# CV_slew_limiter_copy.net
KiCad netlist of a schematic drawn in EAGLE
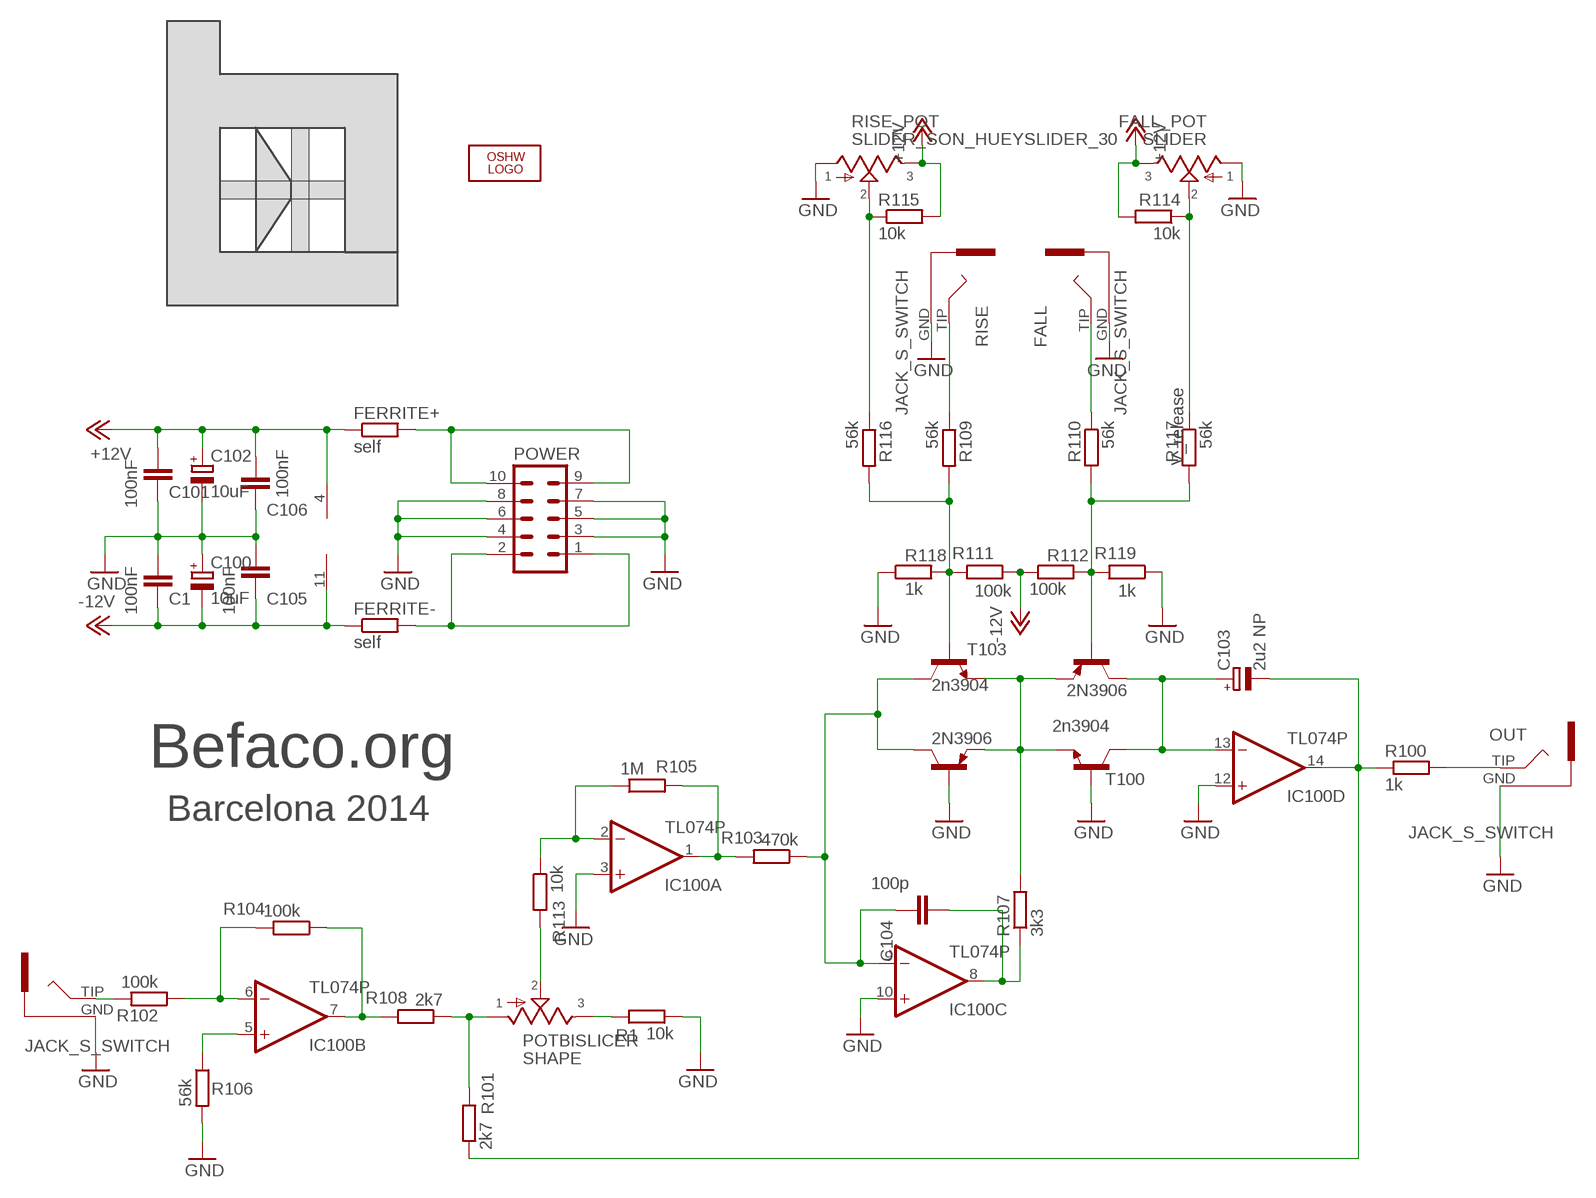
[diagram p0: schematic, sheet 1]

(export (version "E")
  (design (tool "Eeschema 10.0.6"))
  (components
    (comp (ref "C1")
      (value "100nF")
      (footprint "eagle-import:C050-025X075")
      (libsource (lib "eagle-import") (part "C-EU050-025X075"))
    )
    (comp (ref "C100")
      (value "10uF")
      (footprint "eagle-import:E2-4")
      (libsource (lib "eagle-import") (part "CPOL-EUE2-4"))
    )
    (comp (ref "C101")
      (value "100nF")
      (footprint "eagle-import:C050-025X075")
      (libsource (lib "eagle-import") (part "C-EU050-025X075"))
    )
    (comp (ref "C102")
      (value "10uF")
      (footprint "eagle-import:E2-4")
      (libsource (lib "eagle-import") (part "CPOL-EUE2-4"))
    )
    (comp (ref "C103")
      (value "2u2 NP")
      (footprint "eagle-import:E2-4")
      (libsource (lib "eagle-import") (part "CPOL-EUE2-4"))
    )
    (comp (ref "C104")
      (value "100p")
      (footprint "eagle-import:C050-025X075")
      (libsource (lib "eagle-import") (part "C-EU050-025X075"))
    )
    (comp (ref "C105")
      (value "100nF")
      (footprint "eagle-import:C050-025X075")
      (libsource (lib "eagle-import") (part "C-EU050-025X075"))
    )
    (comp (ref "C106")
      (value "100nF")
      (footprint "eagle-import:C050-025X075")
      (libsource (lib "eagle-import") (part "C-EU050-025X075"))
    )
    (comp (ref "FALL")
      (value "JACK_S_SWITCH")
      (footprint "eagle-import:PJ-360_BANANA_2")
      (libsource (lib "eagle-import") (part "JACK_S_SWITCH"))
    )
    (comp (ref "FALL_POT")
      (value "SLIDER")
      (footprint "eagle-import:SILDER_30")
      (libsource (lib "eagle-import") (part "SLIDER_SON_HUEYSLIDER_30"))
    )
    (comp (ref "FERRITE+")
      (value "self")
      (footprint "eagle-import:0204_5")
      (libsource (lib "eagle-import") (part "R-EU_0204/5"))
    )
    (comp (ref "FERRITE-")
      (value "self")
      (footprint "eagle-import:0204_5")
      (libsource (lib "eagle-import") (part "R-EU_0204/5"))
    )
    (comp (ref "IC100")
      (value "TL074P")
      (footprint "eagle-import:DIL14")
      (libsource (lib "eagle-import") (part "TL074P"))
    )
    (comp (ref "IN")
      (value "JACK_S_SWITCH")
      (footprint "eagle-import:PJ-360_BANANA_2")
      (libsource (lib "eagle-import") (part "JACK_S_SWITCH"))
    )
    (comp (ref "LOGO100")
      (value "OSHW_LOGO_8MILX0200-NT")
      (footprint "eagle-import:OSHW_8X200_NOTEXT")
      (libsource (lib "eagle-import") (part "OSHW_LOGO_8MILX0200-NT"))
    )
    (comp (ref "OUT")
      (value "JACK_S_SWITCH")
      (footprint "eagle-import:PJ-360_BANANA_2")
      (libsource (lib "eagle-import") (part "JACK_S_SWITCH"))
    )
    (comp (ref "POWER")
      (value "ML10")
      (footprint "eagle-import:ML10")
      (fields (field (name "OC_FARNELL") "unknown") (field (name "OC_NEWARK") "unknown"))
      (libsource (lib "eagle-import") (part "ML10"))
    )
    (comp (ref "R1")
      (value "10k")
      (footprint "eagle-import:0204_5")
      (libsource (lib "eagle-import") (part "R-EU_0204/5"))
    )
    (comp (ref "R100")
      (value "1k")
      (footprint "eagle-import:0204_5")
      (libsource (lib "eagle-import") (part "R-EU_0204/5"))
    )
    (comp (ref "R101")
      (value "2k7")
      (footprint "eagle-import:0204_5")
      (libsource (lib "eagle-import") (part "R-EU_0204/5"))
    )
    (comp (ref "R102")
      (value "100k")
      (footprint "eagle-import:0204_5")
      (libsource (lib "eagle-import") (part "R-EU_0204/5"))
    )
    (comp (ref "R103")
      (value "470k")
      (footprint "eagle-import:0204_5")
      (libsource (lib "eagle-import") (part "R-EU_0204/5"))
    )
    (comp (ref "R104")
      (value "100k")
      (footprint "eagle-import:0204_5")
      (libsource (lib "eagle-import") (part "R-EU_0204/5"))
    )
    (comp (ref "R105")
      (value "1M")
      (footprint "eagle-import:0204_5")
      (libsource (lib "eagle-import") (part "R-EU_0204/5"))
    )
    (comp (ref "R106")
      (value "56k")
      (footprint "eagle-import:0204_5")
      (libsource (lib "eagle-import") (part "R-EU_0204/5"))
    )
    (comp (ref "R107")
      (value "3k3")
      (footprint "eagle-import:0204_5")
      (libsource (lib "eagle-import") (part "R-EU_0204/5"))
    )
    (comp (ref "R108")
      (value "2k7")
      (footprint "eagle-import:0204_5")
      (libsource (lib "eagle-import") (part "R-EU_0204/5"))
    )
    (comp (ref "R109")
      (value "56k")
      (footprint "eagle-import:0204_5")
      (libsource (lib "eagle-import") (part "R-EU_0204/5"))
    )
    (comp (ref "R110")
      (value "56k")
      (footprint "eagle-import:0204_5")
      (libsource (lib "eagle-import") (part "R-EU_0204/5"))
    )
    (comp (ref "R111")
      (value "100k")
      (footprint "eagle-import:0204_5")
      (libsource (lib "eagle-import") (part "R-EU_0204/5"))
    )
    (comp (ref "R112")
      (value "100k")
      (footprint "eagle-import:0204_5")
      (libsource (lib "eagle-import") (part "R-EU_0204/5"))
    )
    (comp (ref "R113")
      (value "10k")
      (footprint "eagle-import:0204_5")
      (libsource (lib "eagle-import") (part "R-EU_0204/5"))
    )
    (comp (ref "R114")
      (value "10k")
      (footprint "eagle-import:0204_5")
      (libsource (lib "eagle-import") (part "R-EU_0204/5"))
    )
    (comp (ref "R115")
      (value "10k")
      (footprint "eagle-import:0204_5")
      (libsource (lib "eagle-import") (part "R-EU_0204/5"))
    )
    (comp (ref "R116")
      (value "56k")
      (footprint "eagle-import:0204_5")
      (libsource (lib "eagle-import") (part "R-EU_0204/5"))
    )
    (comp (ref "R117")
      (value "56k")
      (footprint "eagle-import:0204_5")
      (libsource (lib "eagle-import") (part "R-EU_0204/5"))
    )
    (comp (ref "R118")
      (value "1k")
      (footprint "eagle-import:0204_5")
      (libsource (lib "eagle-import") (part "R-EU_0204/5"))
    )
    (comp (ref "R119")
      (value "1k")
      (footprint "eagle-import:0204_5")
      (libsource (lib "eagle-import") (part "R-EU_0204/5"))
    )
    (comp (ref "RISE")
      (value "JACK_S_SWITCH")
      (footprint "eagle-import:PJ-360_BANANA_2")
      (libsource (lib "eagle-import") (part "JACK_S_SWITCH"))
    )
    (comp (ref "RISE_POT")
      (value "SLIDER_SON_HUEYSLIDER_30")
      (footprint "eagle-import:SILDER_30")
      (libsource (lib "eagle-import") (part "SLIDER_SON_HUEYSLIDER_30"))
    )
    (comp (ref "SHAPE")
      (value "POTBISLICER")
      (footprint "eagle-import:POTBISLICER")
      (libsource (lib "eagle-import") (part "POTBISLICER"))
    )
    (comp (ref "T100")
      (value "2n3904")
      (footprint "eagle-import:TO92-EBC")
      (libsource (lib "eagle-import") (part "-NPN-TO92-EBC2N3904"))
    )
    (comp (ref "T101")
      (value "2N3906")
      (footprint "eagle-import:TO92-EBC")
      (libsource (lib "eagle-import") (part "-PNP-TO92-EBC2N3906"))
    )
    (comp (ref "T102")
      (value "2N3906")
      (footprint "eagle-import:TO92-EBC")
      (libsource (lib "eagle-import") (part "-PNP-TO92-EBC2N3906"))
    )
    (comp (ref "T103")
      (value "2n3904")
      (footprint "eagle-import:TO92-EBC")
      (libsource (lib "eagle-import") (part "-NPN-TO92-EBC2N3904"))
    )
    (comp (ref "U$100")
      (value "LOGOBEFACOCONLETRAS")
      (footprint "eagle-import:LOGOBEFACOCONLETRAS_2")
      (libsource (lib "eagle-import") (part "LOGOBEFACOCONLETRAS"))
    )
  )
  (nets
    (net (code "1") (name "+12V") (class "Default")
      (node (ref "C101") (pin "2") (pinfunction "2_2") (pintype "passive"))
      (node (ref "C102") (pin "+") (pinfunction "+_+") (pintype "passive"))
      (node (ref "C106") (pin "2") (pinfunction "2_2") (pintype "passive"))
      (node (ref "FALL_POT") (pin "3") (pinfunction "3_3") (pintype "passive"))
      (node (ref "FERRITE+") (pin "1") (pinfunction "1_1") (pintype "passive"))
      (node (ref "IC100") (pin "4") (pinfunction "V+_4") (pintype "power_in"))
      (node (ref "R114") (pin "2") (pinfunction "2_2") (pintype "passive"))
      (node (ref "R115") (pin "2") (pinfunction "2_2") (pintype "passive"))
      (node (ref "RISE_POT") (pin "3") (pinfunction "3_3") (pintype "passive"))
    )
    (net (code "2") (name "-12V") (class "Default")
      (node (ref "C1") (pin "1") (pinfunction "1_1") (pintype "passive"))
      (node (ref "C100") (pin "-") (pinfunction "-_-") (pintype "passive"))
      (node (ref "C105") (pin "1") (pinfunction "1_1") (pintype "passive"))
      (node (ref "FERRITE-") (pin "1") (pinfunction "1_1") (pintype "passive"))
      (node (ref "IC100") (pin "11") (pinfunction "V-_11") (pintype "power_in"))
      (node (ref "R111") (pin "1") (pinfunction "1_1") (pintype "passive"))
      (node (ref "R112") (pin "1") (pinfunction "1_1") (pintype "passive"))
    )
    (net (code "3") (name "GND") (class "Default")
      (node (ref "C1") (pin "2") (pinfunction "2_2") (pintype "passive"))
      (node (ref "C100") (pin "+") (pinfunction "+_+") (pintype "passive"))
      (node (ref "C101") (pin "1") (pinfunction "1_1") (pintype "passive"))
      (node (ref "C102") (pin "-") (pinfunction "-_-") (pintype "passive"))
      (node (ref "C105") (pin "2") (pinfunction "2_2") (pintype "passive"))
      (node (ref "C106") (pin "1") (pinfunction "1_1") (pintype "passive"))
      (node (ref "FALL") (pin "GND") (pinfunction "GND_GND") (pintype "passive"))
      (node (ref "FALL_POT") (pin "1") (pinfunction "1_1") (pintype "passive"))
      (node (ref "IC100") (pin "10") (pinfunction "+IN_10") (pintype "input"))
      (node (ref "IC100") (pin "12") (pinfunction "+IN_12") (pintype "input"))
      (node (ref "IC100") (pin "3") (pinfunction "+IN_3") (pintype "input"))
      (node (ref "IN") (pin "GND") (pinfunction "GND_GND") (pintype "passive"))
      (node (ref "OUT") (pin "GND") (pinfunction "GND_GND") (pintype "passive"))
      (node (ref "POWER") (pin "3") (pinfunction "3_3") (pintype "passive"))
      (node (ref "POWER") (pin "4") (pinfunction "4_4") (pintype "passive"))
      (node (ref "POWER") (pin "5") (pinfunction "5_5") (pintype "passive"))
      (node (ref "POWER") (pin "6") (pinfunction "6_6") (pintype "passive"))
      (node (ref "POWER") (pin "7") (pinfunction "7_7") (pintype "passive"))
      (node (ref "POWER") (pin "8") (pinfunction "8_8") (pintype "passive"))
      (node (ref "R1") (pin "1") (pinfunction "1_1") (pintype "passive"))
      (node (ref "R106") (pin "2") (pinfunction "2_2") (pintype "passive"))
      (node (ref "R118") (pin "1") (pinfunction "1_1") (pintype "passive"))
      (node (ref "R119") (pin "1") (pinfunction "1_1") (pintype "passive"))
      (node (ref "RISE") (pin "GND") (pinfunction "GND_GND") (pintype "passive"))
      (node (ref "RISE_POT") (pin "1") (pinfunction "1_1") (pintype "passive"))
      (node (ref "T100") (pin "B") (pinfunction "B_B") (pintype "passive"))
      (node (ref "T102") (pin "B") (pinfunction "B_B") (pintype "passive"))
    )
    (net (code "4") (name "Net-(FALL-PadTIP)") (class "Default")
      (node (ref "FALL") (pin "TIP") (pinfunction "TIP_TIP") (pintype "passive"))
      (node (ref "R110") (pin "1") (pinfunction "1_1") (pintype "passive"))
    )
    (net (code "5") (name "Net-(FALL_POT-Pad2)") (class "Default")
      (node (ref "FALL_POT") (pin "2") (pinfunction "2_2") (pintype "passive"))
      (node (ref "R114") (pin "1") (pinfunction "1_1") (pintype "passive"))
      (node (ref "R117") (pin "1") (pinfunction "1_1") (pintype "passive"))
    )
    (net (code "6") (name "Net-(FERRITE+-Pad2)") (class "Default")
      (node (ref "FERRITE+") (pin "2") (pinfunction "2_2") (pintype "passive"))
      (node (ref "POWER") (pin "10") (pinfunction "10_10") (pintype "passive"))
      (node (ref "POWER") (pin "9") (pinfunction "9_9") (pintype "passive"))
    )
    (net (code "7") (name "Net-(FERRITE--Pad2)") (class "Default")
      (node (ref "FERRITE-") (pin "2") (pinfunction "2_2") (pintype "passive"))
      (node (ref "POWER") (pin "1") (pinfunction "1_1") (pintype "passive"))
      (node (ref "POWER") (pin "2") (pinfunction "2_2") (pintype "passive"))
    )
    (net (code "8") (name "Net-(IC100A--IN)") (class "Default")
      (node (ref "IC100") (pin "2") (pinfunction "-IN_2") (pintype "input"))
      (node (ref "R105") (pin "1") (pinfunction "1_1") (pintype "passive"))
      (node (ref "R113") (pin "1") (pinfunction "1_1") (pintype "passive"))
    )
    (net (code "9") (name "Net-(IC100A-OUT)") (class "Default")
      (node (ref "IC100") (pin "1") (pinfunction "OUT_1") (pintype "output"))
      (node (ref "R103") (pin "2") (pinfunction "2_2") (pintype "passive"))
      (node (ref "R105") (pin "2") (pinfunction "2_2") (pintype "passive"))
    )
    (net (code "10") (name "Net-(IC100B-+IN)") (class "Default")
      (node (ref "IC100") (pin "5") (pinfunction "+IN_5") (pintype "input"))
      (node (ref "R106") (pin "1") (pinfunction "1_1") (pintype "passive"))
    )
    (net (code "11") (name "Net-(IC100B--IN)") (class "Default")
      (node (ref "IC100") (pin "6") (pinfunction "-IN_6") (pintype "input"))
      (node (ref "R102") (pin "1") (pinfunction "1_1") (pintype "passive"))
      (node (ref "R104") (pin "2") (pinfunction "2_2") (pintype "passive"))
    )
    (net (code "12") (name "Net-(IC100B-OUT)") (class "Default")
      (node (ref "IC100") (pin "7") (pinfunction "OUT_7") (pintype "output"))
      (node (ref "R104") (pin "1") (pinfunction "1_1") (pintype "passive"))
      (node (ref "R108") (pin "2") (pinfunction "2_2") (pintype "passive"))
    )
    (net (code "13") (name "Net-(IC100C--IN)") (class "Default")
      (node (ref "C104") (pin "1") (pinfunction "1_1") (pintype "passive"))
      (node (ref "IC100") (pin "9") (pinfunction "-IN_9") (pintype "input"))
      (node (ref "R103") (pin "1") (pinfunction "1_1") (pintype "passive"))
      (node (ref "T102") (pin "C") (pinfunction "C_C") (pintype "passive"))
      (node (ref "T103") (pin "C") (pinfunction "C_C") (pintype "passive"))
    )
    (net (code "14") (name "Net-(IC100C-OUT)") (class "Default")
      (node (ref "C104") (pin "2") (pinfunction "2_2") (pintype "passive"))
      (node (ref "IC100") (pin "8") (pinfunction "OUT_8") (pintype "output"))
      (node (ref "R107") (pin "1") (pinfunction "1_1") (pintype "passive"))
    )
    (net (code "15") (name "Net-(IC100D--IN)") (class "Default")
      (node (ref "C103") (pin "+") (pinfunction "+_+") (pintype "passive"))
      (node (ref "IC100") (pin "13") (pinfunction "-IN_13") (pintype "input"))
      (node (ref "T100") (pin "C") (pinfunction "C_C") (pintype "passive"))
      (node (ref "T101") (pin "C") (pinfunction "C_C") (pintype "passive"))
    )
    (net (code "16") (name "Net-(IC100D-OUT)") (class "Default")
      (node (ref "C103") (pin "-") (pinfunction "-_-") (pintype "passive"))
      (node (ref "IC100") (pin "14") (pinfunction "OUT_14") (pintype "output"))
      (node (ref "R100") (pin "1") (pinfunction "1_1") (pintype "passive"))
      (node (ref "R101") (pin "1") (pinfunction "1_1") (pintype "passive"))
    )
    (net (code "17") (name "Net-(IN-PadTIP)") (class "Default")
      (node (ref "IN") (pin "TIP") (pinfunction "TIP_TIP") (pintype "passive"))
      (node (ref "R102") (pin "2") (pinfunction "2_2") (pintype "passive"))
    )
    (net (code "18") (name "Net-(OUT-PadTIP)") (class "Default")
      (node (ref "OUT") (pin "TIP") (pinfunction "TIP_TIP") (pintype "passive"))
      (node (ref "R100") (pin "2") (pinfunction "2_2") (pintype "passive"))
    )
    (net (code "19") (name "Net-(R107-Pad2)") (class "Default")
      (node (ref "R107") (pin "2") (pinfunction "2_2") (pintype "passive"))
      (node (ref "T100") (pin "E") (pinfunction "E_E") (pintype "passive"))
      (node (ref "T101") (pin "E") (pinfunction "E_E") (pintype "passive"))
      (node (ref "T102") (pin "E") (pinfunction "E_E") (pintype "passive"))
      (node (ref "T103") (pin "E") (pinfunction "E_E") (pintype "passive"))
    )
    (net (code "20") (name "Net-(R109-Pad1)") (class "Default")
      (node (ref "R109") (pin "1") (pinfunction "1_1") (pintype "passive"))
      (node (ref "RISE") (pin "TIP") (pinfunction "TIP_TIP") (pintype "passive"))
    )
    (net (code "21") (name "Net-(R109-Pad2)") (class "Default")
      (node (ref "R109") (pin "2") (pinfunction "2_2") (pintype "passive"))
      (node (ref "R111") (pin "2") (pinfunction "2_2") (pintype "passive"))
      (node (ref "R116") (pin "2") (pinfunction "2_2") (pintype "passive"))
      (node (ref "R118") (pin "2") (pinfunction "2_2") (pintype "passive"))
      (node (ref "T103") (pin "B") (pinfunction "B_B") (pintype "passive"))
    )
    (net (code "22") (name "Net-(R110-Pad2)") (class "Default")
      (node (ref "R110") (pin "2") (pinfunction "2_2") (pintype "passive"))
      (node (ref "R112") (pin "2") (pinfunction "2_2") (pintype "passive"))
      (node (ref "R117") (pin "2") (pinfunction "2_2") (pintype "passive"))
      (node (ref "R119") (pin "2") (pinfunction "2_2") (pintype "passive"))
      (node (ref "T101") (pin "B") (pinfunction "B_B") (pintype "passive"))
    )
    (net (code "23") (name "Net-(R115-Pad1)") (class "Default")
      (node (ref "R115") (pin "1") (pinfunction "1_1") (pintype "passive"))
      (node (ref "R116") (pin "1") (pinfunction "1_1") (pintype "passive"))
      (node (ref "RISE_POT") (pin "2") (pinfunction "2_2") (pintype "passive"))
    )
    (net (code "24") (name "Net-(SHAPE-1)") (class "Default")
      (node (ref "R101") (pin "2") (pinfunction "2_2") (pintype "passive"))
      (node (ref "R108") (pin "1") (pinfunction "1_1") (pintype "passive"))
      (node (ref "SHAPE") (pin "PIN1") (pinfunction "1_PIN1") (pintype "passive"))
    )
    (net (code "25") (name "Net-(SHAPE-2)") (class "Default")
      (node (ref "R113") (pin "2") (pinfunction "2_2") (pintype "passive"))
      (node (ref "SHAPE") (pin "PIN2") (pinfunction "2_PIN2") (pintype "passive"))
    )
    (net (code "26") (name "Net-(SHAPE-3)") (class "Default")
      (node (ref "R1") (pin "2") (pinfunction "2_2") (pintype "passive"))
      (node (ref "SHAPE") (pin "PIN3") (pinfunction "3_PIN3") (pintype "passive"))
    )
  )
)
